# Tead_Aliens_64A_Display.net
KiCad netlist of a schematic drawn in Altium Designer
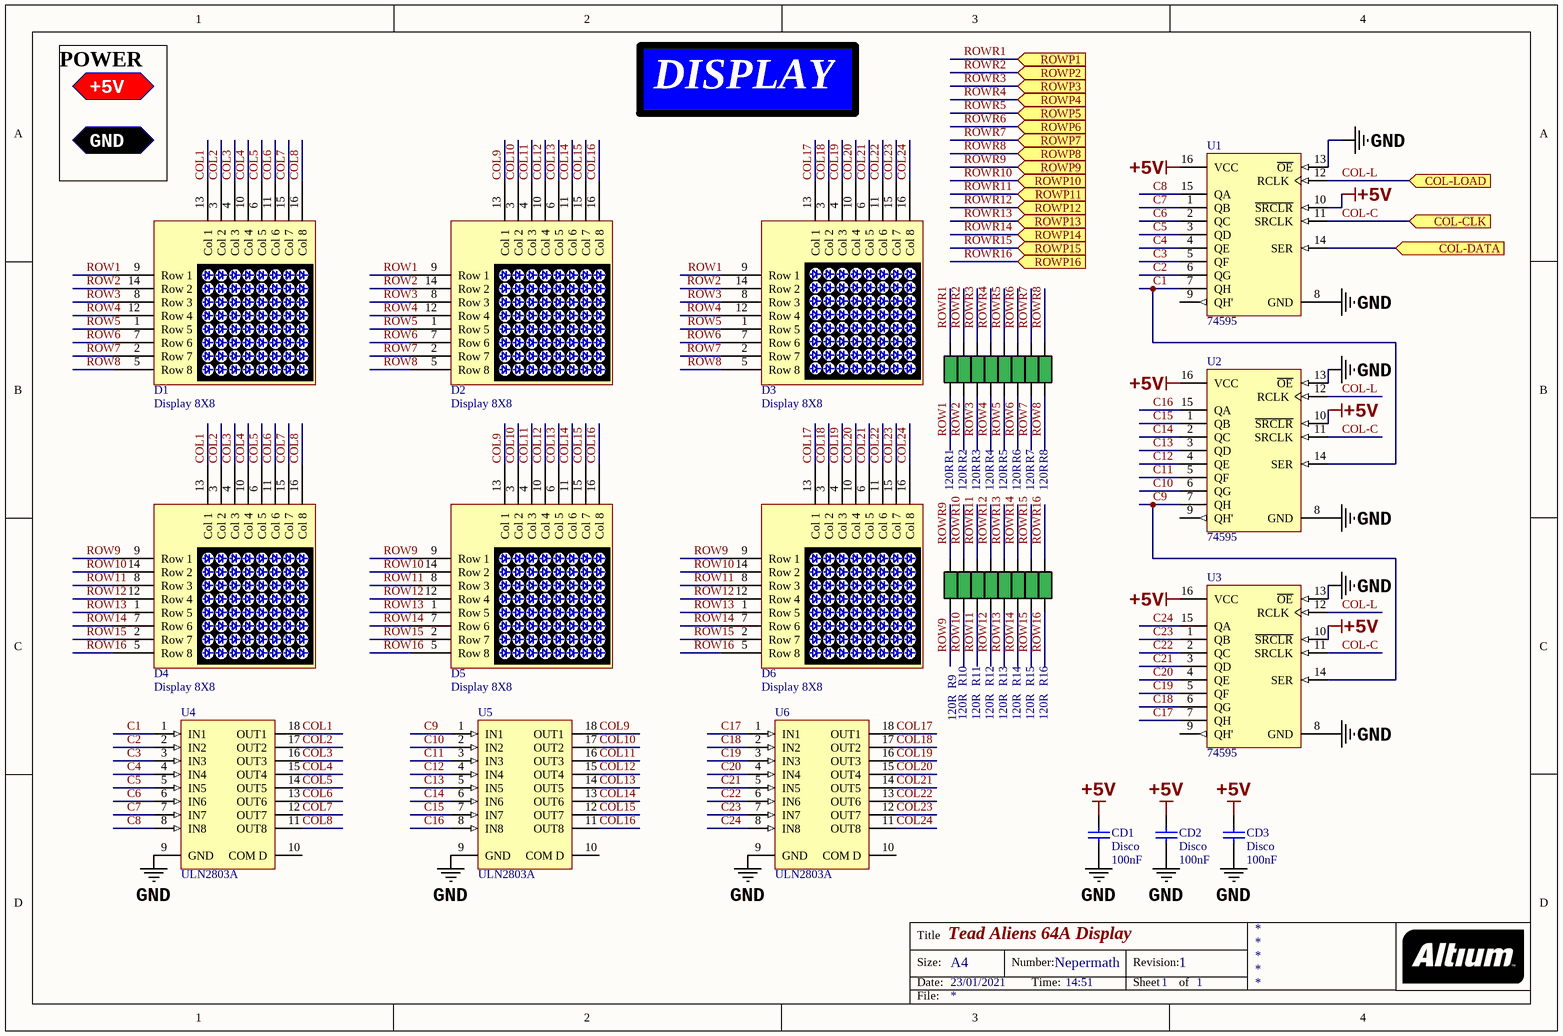
[diagram p0: Tead_Aliens_64A_Display.SchDoc]

(export (version "E")
  (design (tool "Eeschema 10.0.6"))
  (components
    (comp (ref "CD1")
      (value "Disco")
      (footprint "CAP CER DISK 3MM")
      (description "SMD Capacitor 1210 size")
      (fields (field (name "ALTIUM_VALUE") "100nF"))
      (libsource (lib "NEPERMATH") (part "CAP_DISCO"))
    )
    (comp (ref "CD2")
      (value "Disco")
      (footprint "CAP CER DISK 3MM")
      (description "SMD Capacitor 1210 size")
      (fields (field (name "ALTIUM_VALUE") "100nF"))
      (libsource (lib "NEPERMATH") (part "CAP_DISCO"))
    )
    (comp (ref "CD3")
      (value "Disco")
      (footprint "CAP CER DISK 3MM")
      (description "SMD Capacitor 1210 size")
      (fields (field (name "ALTIUM_VALUE") "100nF"))
      (libsource (lib "NEPERMATH") (part "CAP_DISCO"))
    )
    (comp (ref "D1")
      (value "Display 8X8")
      (footprint "DISPLAY_2088BS_DIP_2X8")
      (description "Display Dot LED 8x8  60mm X 60 mm")
      (libsource (lib "NEPERMATH") (part "Display 2088BS 8x8 60mm X 60 mm"))
    )
    (comp (ref "D2")
      (value "Display 8X8")
      (footprint "DISPLAY_2088BS_DIP_2X8")
      (description "Display Dot LED 8x8  60mm X 60 mm")
      (libsource (lib "NEPERMATH") (part "Display 2088BS 8x8 60mm X 60 mm"))
    )
    (comp (ref "D3")
      (value "Display 8X8")
      (footprint "DISPLAY_2088BS_DIP_2X8")
      (description "Display Dot LED 8x8  60mm X 60 mm")
      (libsource (lib "NEPERMATH") (part "Display 2088BS 8x8 60mm X 60 mm"))
    )
    (comp (ref "D4")
      (value "Display 8X8")
      (footprint "DISPLAY_2088BS_DIP_2X8")
      (description "Display Dot LED 8x8  60mm X 60 mm")
      (libsource (lib "NEPERMATH") (part "Display 2088BS 8x8 60mm X 60 mm"))
    )
    (comp (ref "D5")
      (value "Display 8X8")
      (footprint "DISPLAY_2088BS_DIP_2X8")
      (description "Display Dot LED 8x8  60mm X 60 mm")
      (libsource (lib "NEPERMATH") (part "Display 2088BS 8x8 60mm X 60 mm"))
    )
    (comp (ref "D6")
      (value "Display 8X8")
      (footprint "DISPLAY_2088BS_DIP_2X8")
      (description "Display Dot LED 8x8  60mm X 60 mm")
      (libsource (lib "NEPERMATH") (part "Display 2088BS 8x8 60mm X 60 mm"))
    )
    (comp (ref "R1")
      (value "120R")
      (footprint "RES_0805")
      (description "Generic Resistor")
      (fields (field (name "Comment") "Resistor Generic"))
      (libsource (lib "NEPERMATH") (part "Resistor Generic"))
    )
    (comp (ref "R2")
      (value "120R")
      (footprint "RES_0805")
      (description "Generic Resistor")
      (fields (field (name "Comment") "Resistor Generic"))
      (libsource (lib "NEPERMATH") (part "Resistor Generic"))
    )
    (comp (ref "R3")
      (value "120R")
      (footprint "RES_0805")
      (description "Generic Resistor")
      (fields (field (name "Comment") "Resistor Generic"))
      (libsource (lib "NEPERMATH") (part "Resistor Generic"))
    )
    (comp (ref "R4")
      (value "120R")
      (footprint "RES_0805")
      (description "Generic Resistor")
      (fields (field (name "Comment") "Resistor Generic"))
      (libsource (lib "NEPERMATH") (part "Resistor Generic"))
    )
    (comp (ref "R5")
      (value "120R")
      (footprint "RES_0805")
      (description "Generic Resistor")
      (fields (field (name "Comment") "Resistor Generic"))
      (libsource (lib "NEPERMATH") (part "Resistor Generic"))
    )
    (comp (ref "R6")
      (value "120R")
      (footprint "RES_0805")
      (description "Generic Resistor")
      (fields (field (name "Comment") "Resistor Generic"))
      (libsource (lib "NEPERMATH") (part "Resistor Generic"))
    )
    (comp (ref "R7")
      (value "120R")
      (footprint "RES_0805")
      (description "Generic Resistor")
      (fields (field (name "Comment") "Resistor Generic"))
      (libsource (lib "NEPERMATH") (part "Resistor Generic"))
    )
    (comp (ref "R8")
      (value "120R")
      (footprint "RES_0805")
      (description "Generic Resistor")
      (fields (field (name "Comment") "Resistor Generic"))
      (libsource (lib "NEPERMATH") (part "Resistor Generic"))
    )
    (comp (ref "R9")
      (value "120R")
      (footprint "RES_0805")
      (description "Generic Resistor")
      (fields (field (name "Comment") "Resistor Generic"))
      (libsource (lib "NEPERMATH") (part "Resistor Generic"))
    )
    (comp (ref "R10")
      (value "120R")
      (footprint "RES_0805")
      (description "Generic Resistor")
      (fields (field (name "Comment") "Resistor Generic"))
      (libsource (lib "NEPERMATH") (part "Resistor Generic"))
    )
    (comp (ref "R11")
      (value "120R")
      (footprint "RES_0805")
      (description "Generic Resistor")
      (fields (field (name "Comment") "Resistor Generic"))
      (libsource (lib "NEPERMATH") (part "Resistor Generic"))
    )
    (comp (ref "R12")
      (value "120R")
      (footprint "RES_0805")
      (description "Generic Resistor")
      (fields (field (name "Comment") "Resistor Generic"))
      (libsource (lib "NEPERMATH") (part "Resistor Generic"))
    )
    (comp (ref "R13")
      (value "120R")
      (footprint "RES_0805")
      (description "Generic Resistor")
      (fields (field (name "Comment") "Resistor Generic"))
      (libsource (lib "NEPERMATH") (part "Resistor Generic"))
    )
    (comp (ref "R14")
      (value "120R")
      (footprint "RES_0805")
      (description "Generic Resistor")
      (fields (field (name "Comment") "Resistor Generic"))
      (libsource (lib "NEPERMATH") (part "Resistor Generic"))
    )
    (comp (ref "R15")
      (value "120R")
      (footprint "RES_0805")
      (description "Generic Resistor")
      (fields (field (name "Comment") "Resistor Generic"))
      (libsource (lib "NEPERMATH") (part "Resistor Generic"))
    )
    (comp (ref "R16")
      (value "120R")
      (footprint "RES_0805")
      (description "Generic Resistor")
      (fields (field (name "Comment") "Resistor Generic"))
      (libsource (lib "NEPERMATH") (part "Resistor Generic"))
    )
    (comp (ref "U1")
      (value "74595")
      (footprint "DIP16")
      (description "74595 Generico L,H,LC,HC,F,LS")
      (libsource (lib "NEPERMATH") (part "74595 Generico L,H,HC,F,LS"))
    )
    (comp (ref "U2")
      (value "74595")
      (footprint "DIP16")
      (description "74595 Generico L,H,LC,HC,F,LS")
      (libsource (lib "NEPERMATH") (part "74595 Generico L,H,HC,F,LS"))
    )
    (comp (ref "U3")
      (value "74595")
      (footprint "DIP16")
      (description "74595 Generico L,H,LC,HC,F,LS")
      (libsource (lib "NEPERMATH") (part "74595 Generico L,H,HC,F,LS"))
    )
    (comp (ref "U4")
      (value "ULN2803A")
      (footprint "DIP18")
      (description "Eight Darlington Array")
      (fields (field (name "PUBLISHER") "Altium Limited"))
      (libsource (lib "NEPERMATH") (part "ULN2803A"))
    )
    (comp (ref "U5")
      (value "ULN2803A")
      (footprint "DIP18")
      (description "Eight Darlington Array")
      (fields (field (name "PUBLISHER") "Altium Limited"))
      (libsource (lib "NEPERMATH") (part "ULN2803A"))
    )
    (comp (ref "U6")
      (value "ULN2803A")
      (footprint "DIP18")
      (description "Eight Darlington Array")
      (fields (field (name "PUBLISHER") "Altium Limited"))
      (libsource (lib "NEPERMATH") (part "ULN2803A"))
    )
  )
  (nets
    (net (code "1") (name "+5V") (class "Default")
      (node (ref "CD1") (pin "1") (pinfunction "1_1") (pintype "passive"))
      (node (ref "CD2") (pin "1") (pinfunction "1_1") (pintype "passive"))
      (node (ref "CD3") (pin "1") (pinfunction "1_1") (pintype "passive"))
      (node (ref "U1") (pin "10") (pinfunction "~{SRCLR}_10") (pintype "input"))
      (node (ref "U1") (pin "16") (pinfunction "VCC_16") (pintype "power_in"))
      (node (ref "U2") (pin "10") (pinfunction "~{SRCLR}_10") (pintype "input"))
      (node (ref "U2") (pin "16") (pinfunction "VCC_16") (pintype "power_in"))
      (node (ref "U3") (pin "10") (pinfunction "~{SRCLR}_10") (pintype "input"))
      (node (ref "U3") (pin "16") (pinfunction "VCC_16") (pintype "power_in"))
    )
    (net (code "2") (name "/C1") (class "Default")
      (node (ref "U1") (pin "7") (pinfunction "QH_7") (pintype "tri_state"))
      (node (ref "U2") (pin "14") (pinfunction "SER_14") (pintype "input"))
      (node (ref "U4") (pin "1") (pinfunction "IN1_1") (pintype "input"))
    )
    (net (code "3") (name "/C2") (class "Default")
      (node (ref "U1") (pin "6") (pinfunction "QG_6") (pintype "tri_state"))
      (node (ref "U4") (pin "2") (pinfunction "IN2_2") (pintype "input"))
    )
    (net (code "4") (name "/C3") (class "Default")
      (node (ref "U1") (pin "5") (pinfunction "QF_5") (pintype "tri_state"))
      (node (ref "U4") (pin "3") (pinfunction "IN3_3") (pintype "input"))
    )
    (net (code "5") (name "/C4") (class "Default")
      (node (ref "U1") (pin "4") (pinfunction "QE_4") (pintype "tri_state"))
      (node (ref "U4") (pin "4") (pinfunction "IN4_4") (pintype "input"))
    )
    (net (code "6") (name "/C5") (class "Default")
      (node (ref "U1") (pin "3") (pinfunction "QD_3") (pintype "tri_state"))
      (node (ref "U4") (pin "5") (pinfunction "IN5_5") (pintype "input"))
    )
    (net (code "7") (name "/C6") (class "Default")
      (node (ref "U1") (pin "2") (pinfunction "QC_2") (pintype "tri_state"))
      (node (ref "U4") (pin "6") (pinfunction "IN6_6") (pintype "input"))
    )
    (net (code "8") (name "/C7") (class "Default")
      (node (ref "U1") (pin "1") (pinfunction "QB_1") (pintype "tri_state"))
      (node (ref "U4") (pin "7") (pinfunction "IN7_7") (pintype "input"))
    )
    (net (code "9") (name "/C8") (class "Default")
      (node (ref "U1") (pin "15") (pinfunction "QA_15") (pintype "tri_state"))
      (node (ref "U4") (pin "8") (pinfunction "IN8_8") (pintype "input"))
    )
    (net (code "10") (name "/C9") (class "Default")
      (node (ref "U2") (pin "7") (pinfunction "QH_7") (pintype "tri_state"))
      (node (ref "U3") (pin "14") (pinfunction "SER_14") (pintype "input"))
      (node (ref "U5") (pin "1") (pinfunction "IN1_1") (pintype "input"))
    )
    (net (code "11") (name "/C10") (class "Default")
      (node (ref "U2") (pin "6") (pinfunction "QG_6") (pintype "tri_state"))
      (node (ref "U5") (pin "2") (pinfunction "IN2_2") (pintype "input"))
    )
    (net (code "12") (name "/C11") (class "Default")
      (node (ref "U2") (pin "5") (pinfunction "QF_5") (pintype "tri_state"))
      (node (ref "U5") (pin "3") (pinfunction "IN3_3") (pintype "input"))
    )
    (net (code "13") (name "/C12") (class "Default")
      (node (ref "U2") (pin "4") (pinfunction "QE_4") (pintype "tri_state"))
      (node (ref "U5") (pin "4") (pinfunction "IN4_4") (pintype "input"))
    )
    (net (code "14") (name "/C13") (class "Default")
      (node (ref "U2") (pin "3") (pinfunction "QD_3") (pintype "tri_state"))
      (node (ref "U5") (pin "5") (pinfunction "IN5_5") (pintype "input"))
    )
    (net (code "15") (name "/C14") (class "Default")
      (node (ref "U2") (pin "2") (pinfunction "QC_2") (pintype "tri_state"))
      (node (ref "U5") (pin "6") (pinfunction "IN6_6") (pintype "input"))
    )
    (net (code "16") (name "/C15") (class "Default")
      (node (ref "U2") (pin "1") (pinfunction "QB_1") (pintype "tri_state"))
      (node (ref "U5") (pin "7") (pinfunction "IN7_7") (pintype "input"))
    )
    (net (code "17") (name "/C16") (class "Default")
      (node (ref "U2") (pin "15") (pinfunction "QA_15") (pintype "tri_state"))
      (node (ref "U5") (pin "8") (pinfunction "IN8_8") (pintype "input"))
    )
    (net (code "18") (name "/C17") (class "Default")
      (node (ref "U3") (pin "7") (pinfunction "QH_7") (pintype "tri_state"))
      (node (ref "U6") (pin "1") (pinfunction "IN1_1") (pintype "input"))
    )
    (net (code "19") (name "/C18") (class "Default")
      (node (ref "U3") (pin "6") (pinfunction "QG_6") (pintype "tri_state"))
      (node (ref "U6") (pin "2") (pinfunction "IN2_2") (pintype "input"))
    )
    (net (code "20") (name "/C19") (class "Default")
      (node (ref "U3") (pin "5") (pinfunction "QF_5") (pintype "tri_state"))
      (node (ref "U6") (pin "3") (pinfunction "IN3_3") (pintype "input"))
    )
    (net (code "21") (name "/C20") (class "Default")
      (node (ref "U3") (pin "4") (pinfunction "QE_4") (pintype "tri_state"))
      (node (ref "U6") (pin "4") (pinfunction "IN4_4") (pintype "input"))
    )
    (net (code "22") (name "/C21") (class "Default")
      (node (ref "U3") (pin "3") (pinfunction "QD_3") (pintype "tri_state"))
      (node (ref "U6") (pin "5") (pinfunction "IN5_5") (pintype "input"))
    )
    (net (code "23") (name "/C22") (class "Default")
      (node (ref "U3") (pin "2") (pinfunction "QC_2") (pintype "tri_state"))
      (node (ref "U6") (pin "6") (pinfunction "IN6_6") (pintype "input"))
    )
    (net (code "24") (name "/C23") (class "Default")
      (node (ref "U3") (pin "1") (pinfunction "QB_1") (pintype "tri_state"))
      (node (ref "U6") (pin "7") (pinfunction "IN7_7") (pintype "input"))
    )
    (net (code "25") (name "/C24") (class "Default")
      (node (ref "U3") (pin "15") (pinfunction "QA_15") (pintype "tri_state"))
      (node (ref "U6") (pin "8") (pinfunction "IN8_8") (pintype "input"))
    )
    (net (code "26") (name "/COL-C") (class "Default")
      (node (ref "U1") (pin "11") (pinfunction "SRCLK_11") (pintype "input"))
      (node (ref "U2") (pin "11") (pinfunction "SRCLK_11") (pintype "input"))
      (node (ref "U3") (pin "11") (pinfunction "SRCLK_11") (pintype "input"))
    )
    (net (code "27") (name "/COL-DATA") (class "Default")
      (node (ref "U1") (pin "14") (pinfunction "SER_14") (pintype "input"))
    )
    (net (code "28") (name "/COL-L") (class "Default")
      (node (ref "U1") (pin "12") (pinfunction "RCLK_12") (pintype "input"))
      (node (ref "U2") (pin "12") (pinfunction "RCLK_12") (pintype "input"))
      (node (ref "U3") (pin "12") (pinfunction "RCLK_12") (pintype "input"))
    )
    (net (code "29") (name "/COL1") (class "Default")
      (node (ref "D1") (pin "13") (pinfunction "Col_1_13") (pintype "passive"))
      (node (ref "D4") (pin "13") (pinfunction "Col_1_13") (pintype "passive"))
      (node (ref "U4") (pin "18") (pinfunction "OUT1_18") (pintype "open_collector"))
    )
    (net (code "30") (name "/COL2") (class "Default")
      (node (ref "D1") (pin "3") (pinfunction "Col_2_3") (pintype "passive"))
      (node (ref "D4") (pin "3") (pinfunction "Col_2_3") (pintype "passive"))
      (node (ref "U4") (pin "17") (pinfunction "OUT2_17") (pintype "open_collector"))
    )
    (net (code "31") (name "/COL3") (class "Default")
      (node (ref "D1") (pin "4") (pinfunction "Col_3_4") (pintype "passive"))
      (node (ref "D4") (pin "4") (pinfunction "Col_3_4") (pintype "passive"))
      (node (ref "U4") (pin "16") (pinfunction "OUT3_16") (pintype "open_collector"))
    )
    (net (code "32") (name "/COL4") (class "Default")
      (node (ref "D1") (pin "10") (pinfunction "Col_4_10") (pintype "passive"))
      (node (ref "D4") (pin "10") (pinfunction "Col_4_10") (pintype "passive"))
      (node (ref "U4") (pin "15") (pinfunction "OUT4_15") (pintype "open_collector"))
    )
    (net (code "33") (name "/COL5") (class "Default")
      (node (ref "D1") (pin "6") (pinfunction "Col_5_6") (pintype "passive"))
      (node (ref "D4") (pin "6") (pinfunction "Col_5_6") (pintype "passive"))
      (node (ref "U4") (pin "14") (pinfunction "OUT5_14") (pintype "open_collector"))
    )
    (net (code "34") (name "/COL6") (class "Default")
      (node (ref "D1") (pin "11") (pinfunction "Col_6_11") (pintype "passive"))
      (node (ref "D4") (pin "11") (pinfunction "Col_6_11") (pintype "passive"))
      (node (ref "U4") (pin "13") (pinfunction "OUT6_13") (pintype "open_collector"))
    )
    (net (code "35") (name "/COL7") (class "Default")
      (node (ref "D1") (pin "15") (pinfunction "Col_7_15") (pintype "passive"))
      (node (ref "D4") (pin "15") (pinfunction "Col_7_15") (pintype "passive"))
      (node (ref "U4") (pin "12") (pinfunction "OUT7_12") (pintype "open_collector"))
    )
    (net (code "36") (name "/COL8") (class "Default")
      (node (ref "D1") (pin "16") (pinfunction "Col_8_16") (pintype "passive"))
      (node (ref "D4") (pin "16") (pinfunction "Col_8_16") (pintype "passive"))
      (node (ref "U4") (pin "11") (pinfunction "OUT8_11") (pintype "open_collector"))
    )
    (net (code "37") (name "/COL9") (class "Default")
      (node (ref "D2") (pin "13") (pinfunction "Col_1_13") (pintype "passive"))
      (node (ref "D5") (pin "13") (pinfunction "Col_1_13") (pintype "passive"))
      (node (ref "U5") (pin "18") (pinfunction "OUT1_18") (pintype "open_collector"))
    )
    (net (code "38") (name "/COL10") (class "Default")
      (node (ref "D2") (pin "3") (pinfunction "Col_2_3") (pintype "passive"))
      (node (ref "D5") (pin "3") (pinfunction "Col_2_3") (pintype "passive"))
      (node (ref "U5") (pin "17") (pinfunction "OUT2_17") (pintype "open_collector"))
    )
    (net (code "39") (name "/COL11") (class "Default")
      (node (ref "D2") (pin "4") (pinfunction "Col_3_4") (pintype "passive"))
      (node (ref "D5") (pin "4") (pinfunction "Col_3_4") (pintype "passive"))
      (node (ref "U5") (pin "16") (pinfunction "OUT3_16") (pintype "open_collector"))
    )
    (net (code "40") (name "/COL12") (class "Default")
      (node (ref "D2") (pin "10") (pinfunction "Col_4_10") (pintype "passive"))
      (node (ref "D5") (pin "10") (pinfunction "Col_4_10") (pintype "passive"))
      (node (ref "U5") (pin "15") (pinfunction "OUT4_15") (pintype "open_collector"))
    )
    (net (code "41") (name "/COL13") (class "Default")
      (node (ref "D2") (pin "6") (pinfunction "Col_5_6") (pintype "passive"))
      (node (ref "D5") (pin "6") (pinfunction "Col_5_6") (pintype "passive"))
      (node (ref "U5") (pin "14") (pinfunction "OUT5_14") (pintype "open_collector"))
    )
    (net (code "42") (name "/COL14") (class "Default")
      (node (ref "D2") (pin "11") (pinfunction "Col_6_11") (pintype "passive"))
      (node (ref "D5") (pin "11") (pinfunction "Col_6_11") (pintype "passive"))
      (node (ref "U5") (pin "13") (pinfunction "OUT6_13") (pintype "open_collector"))
    )
    (net (code "43") (name "/COL15") (class "Default")
      (node (ref "D2") (pin "15") (pinfunction "Col_7_15") (pintype "passive"))
      (node (ref "D5") (pin "15") (pinfunction "Col_7_15") (pintype "passive"))
      (node (ref "U5") (pin "12") (pinfunction "OUT7_12") (pintype "open_collector"))
    )
    (net (code "44") (name "/COL16") (class "Default")
      (node (ref "D2") (pin "16") (pinfunction "Col_8_16") (pintype "passive"))
      (node (ref "D5") (pin "16") (pinfunction "Col_8_16") (pintype "passive"))
      (node (ref "U5") (pin "11") (pinfunction "OUT8_11") (pintype "open_collector"))
    )
    (net (code "45") (name "/COL17") (class "Default")
      (node (ref "D3") (pin "13") (pinfunction "Col_1_13") (pintype "passive"))
      (node (ref "D6") (pin "13") (pinfunction "Col_1_13") (pintype "passive"))
      (node (ref "U6") (pin "18") (pinfunction "OUT1_18") (pintype "open_collector"))
    )
    (net (code "46") (name "/COL18") (class "Default")
      (node (ref "D3") (pin "3") (pinfunction "Col_2_3") (pintype "passive"))
      (node (ref "D6") (pin "3") (pinfunction "Col_2_3") (pintype "passive"))
      (node (ref "U6") (pin "17") (pinfunction "OUT2_17") (pintype "open_collector"))
    )
    (net (code "47") (name "/COL19") (class "Default")
      (node (ref "D3") (pin "4") (pinfunction "Col_3_4") (pintype "passive"))
      (node (ref "D6") (pin "4") (pinfunction "Col_3_4") (pintype "passive"))
      (node (ref "U6") (pin "16") (pinfunction "OUT3_16") (pintype "open_collector"))
    )
    (net (code "48") (name "/COL20") (class "Default")
      (node (ref "D3") (pin "10") (pinfunction "Col_4_10") (pintype "passive"))
      (node (ref "D6") (pin "10") (pinfunction "Col_4_10") (pintype "passive"))
      (node (ref "U6") (pin "15") (pinfunction "OUT4_15") (pintype "open_collector"))
    )
    (net (code "49") (name "/COL21") (class "Default")
      (node (ref "D3") (pin "6") (pinfunction "Col_5_6") (pintype "passive"))
      (node (ref "D6") (pin "6") (pinfunction "Col_5_6") (pintype "passive"))
      (node (ref "U6") (pin "14") (pinfunction "OUT5_14") (pintype "open_collector"))
    )
    (net (code "50") (name "/COL22") (class "Default")
      (node (ref "D3") (pin "11") (pinfunction "Col_6_11") (pintype "passive"))
      (node (ref "D6") (pin "11") (pinfunction "Col_6_11") (pintype "passive"))
      (node (ref "U6") (pin "13") (pinfunction "OUT6_13") (pintype "open_collector"))
    )
    (net (code "51") (name "/COL23") (class "Default")
      (node (ref "D3") (pin "15") (pinfunction "Col_7_15") (pintype "passive"))
      (node (ref "D6") (pin "15") (pinfunction "Col_7_15") (pintype "passive"))
      (node (ref "U6") (pin "12") (pinfunction "OUT7_12") (pintype "open_collector"))
    )
    (net (code "52") (name "/COL24") (class "Default")
      (node (ref "D3") (pin "16") (pinfunction "Col_8_16") (pintype "passive"))
      (node (ref "D6") (pin "16") (pinfunction "Col_8_16") (pintype "passive"))
      (node (ref "U6") (pin "11") (pinfunction "OUT8_11") (pintype "open_collector"))
    )
    (net (code "53") (name "/ROW1") (class "Default")
      (node (ref "D1") (pin "9") (pinfunction "Row_1_9") (pintype "passive"))
      (node (ref "D2") (pin "9") (pinfunction "Row_1_9") (pintype "passive"))
      (node (ref "D3") (pin "9") (pinfunction "Row_1_9") (pintype "passive"))
      (node (ref "R1") (pin "1") (pinfunction "1_1") (pintype "passive"))
    )
    (net (code "54") (name "/ROW2") (class "Default")
      (node (ref "D1") (pin "14") (pinfunction "Row_2_14") (pintype "passive"))
      (node (ref "D2") (pin "14") (pinfunction "Row_2_14") (pintype "passive"))
      (node (ref "D3") (pin "14") (pinfunction "Row_2_14") (pintype "passive"))
      (node (ref "R2") (pin "1") (pinfunction "1_1") (pintype "passive"))
    )
    (net (code "55") (name "/ROW3") (class "Default")
      (node (ref "D1") (pin "8") (pinfunction "Row_3_8") (pintype "passive"))
      (node (ref "D2") (pin "8") (pinfunction "Row_3_8") (pintype "passive"))
      (node (ref "D3") (pin "8") (pinfunction "Row_3_8") (pintype "passive"))
      (node (ref "R3") (pin "1") (pinfunction "1_1") (pintype "passive"))
    )
    (net (code "56") (name "/ROW4") (class "Default")
      (node (ref "D1") (pin "12") (pinfunction "Row_4_12") (pintype "passive"))
      (node (ref "D2") (pin "12") (pinfunction "Row_4_12") (pintype "passive"))
      (node (ref "D3") (pin "12") (pinfunction "Row_4_12") (pintype "passive"))
      (node (ref "R4") (pin "1") (pinfunction "1_1") (pintype "passive"))
    )
    (net (code "57") (name "/ROW5") (class "Default")
      (node (ref "D1") (pin "1") (pinfunction "Row_5_1") (pintype "passive"))
      (node (ref "D2") (pin "1") (pinfunction "Row_5_1") (pintype "passive"))
      (node (ref "D3") (pin "1") (pinfunction "Row_5_1") (pintype "passive"))
      (node (ref "R5") (pin "1") (pinfunction "1_1") (pintype "passive"))
    )
    (net (code "58") (name "/ROW6") (class "Default")
      (node (ref "D1") (pin "7") (pinfunction "Row_6_7") (pintype "passive"))
      (node (ref "D2") (pin "7") (pinfunction "Row_6_7") (pintype "passive"))
      (node (ref "D3") (pin "7") (pinfunction "Row_6_7") (pintype "passive"))
      (node (ref "R6") (pin "1") (pinfunction "1_1") (pintype "passive"))
    )
    (net (code "59") (name "/ROW7") (class "Default")
      (node (ref "D1") (pin "2") (pinfunction "Row_7_2") (pintype "passive"))
      (node (ref "D2") (pin "2") (pinfunction "Row_7_2") (pintype "passive"))
      (node (ref "D3") (pin "2") (pinfunction "Row_7_2") (pintype "passive"))
      (node (ref "R7") (pin "1") (pinfunction "1_1") (pintype "passive"))
    )
    (net (code "60") (name "/ROW8") (class "Default")
      (node (ref "D1") (pin "5") (pinfunction "Row_8_5") (pintype "passive"))
      (node (ref "D2") (pin "5") (pinfunction "Row_8_5") (pintype "passive"))
      (node (ref "D3") (pin "5") (pinfunction "Row_8_5") (pintype "passive"))
      (node (ref "R8") (pin "1") (pinfunction "1_1") (pintype "passive"))
    )
    (net (code "61") (name "/ROW9") (class "Default")
      (node (ref "D4") (pin "9") (pinfunction "Row_1_9") (pintype "passive"))
      (node (ref "D5") (pin "9") (pinfunction "Row_1_9") (pintype "passive"))
      (node (ref "D6") (pin "9") (pinfunction "Row_1_9") (pintype "passive"))
      (node (ref "R9") (pin "1") (pinfunction "1_1") (pintype "passive"))
    )
    (net (code "62") (name "/ROW10") (class "Default")
      (node (ref "D4") (pin "14") (pinfunction "Row_2_14") (pintype "passive"))
      (node (ref "D5") (pin "14") (pinfunction "Row_2_14") (pintype "passive"))
      (node (ref "D6") (pin "14") (pinfunction "Row_2_14") (pintype "passive"))
      (node (ref "R10") (pin "1") (pinfunction "1_1") (pintype "passive"))
    )
    (net (code "63") (name "/ROW11") (class "Default")
      (node (ref "D4") (pin "8") (pinfunction "Row_3_8") (pintype "passive"))
      (node (ref "D5") (pin "8") (pinfunction "Row_3_8") (pintype "passive"))
      (node (ref "D6") (pin "8") (pinfunction "Row_3_8") (pintype "passive"))
      (node (ref "R11") (pin "1") (pinfunction "1_1") (pintype "passive"))
    )
    (net (code "64") (name "/ROW12") (class "Default")
      (node (ref "D4") (pin "12") (pinfunction "Row_4_12") (pintype "passive"))
      (node (ref "D5") (pin "12") (pinfunction "Row_4_12") (pintype "passive"))
      (node (ref "D6") (pin "12") (pinfunction "Row_4_12") (pintype "passive"))
      (node (ref "R12") (pin "1") (pinfunction "1_1") (pintype "passive"))
    )
    (net (code "65") (name "/ROW13") (class "Default")
      (node (ref "D4") (pin "1") (pinfunction "Row_5_1") (pintype "passive"))
      (node (ref "D5") (pin "1") (pinfunction "Row_5_1") (pintype "passive"))
      (node (ref "D6") (pin "1") (pinfunction "Row_5_1") (pintype "passive"))
      (node (ref "R13") (pin "1") (pinfunction "1_1") (pintype "passive"))
    )
    (net (code "66") (name "/ROW14") (class "Default")
      (node (ref "D4") (pin "7") (pinfunction "Row_6_7") (pintype "passive"))
      (node (ref "D5") (pin "7") (pinfunction "Row_6_7") (pintype "passive"))
      (node (ref "D6") (pin "7") (pinfunction "Row_6_7") (pintype "passive"))
      (node (ref "R14") (pin "1") (pinfunction "1_1") (pintype "passive"))
    )
    (net (code "67") (name "/ROW15") (class "Default")
      (node (ref "D4") (pin "2") (pinfunction "Row_7_2") (pintype "passive"))
      (node (ref "D5") (pin "2") (pinfunction "Row_7_2") (pintype "passive"))
      (node (ref "D6") (pin "2") (pinfunction "Row_7_2") (pintype "passive"))
      (node (ref "R15") (pin "1") (pinfunction "1_1") (pintype "passive"))
    )
    (net (code "68") (name "/ROW16") (class "Default")
      (node (ref "D4") (pin "5") (pinfunction "Row_8_5") (pintype "passive"))
      (node (ref "D5") (pin "5") (pinfunction "Row_8_5") (pintype "passive"))
      (node (ref "D6") (pin "5") (pinfunction "Row_8_5") (pintype "passive"))
      (node (ref "R16") (pin "1") (pinfunction "1_1") (pintype "passive"))
    )
    (net (code "69") (name "/ROWR1") (class "Default")
      (node (ref "R1") (pin "2") (pinfunction "2_2") (pintype "passive"))
    )
    (net (code "70") (name "/ROWR2") (class "Default")
      (node (ref "R2") (pin "2") (pinfunction "2_2") (pintype "passive"))
    )
    (net (code "71") (name "/ROWR3") (class "Default")
      (node (ref "R3") (pin "2") (pinfunction "2_2") (pintype "passive"))
    )
    (net (code "72") (name "/ROWR4") (class "Default")
      (node (ref "R4") (pin "2") (pinfunction "2_2") (pintype "passive"))
    )
    (net (code "73") (name "/ROWR5") (class "Default")
      (node (ref "R5") (pin "2") (pinfunction "2_2") (pintype "passive"))
    )
    (net (code "74") (name "/ROWR6") (class "Default")
      (node (ref "R6") (pin "2") (pinfunction "2_2") (pintype "passive"))
    )
    (net (code "75") (name "/ROWR7") (class "Default")
      (node (ref "R7") (pin "2") (pinfunction "2_2") (pintype "passive"))
    )
    (net (code "76") (name "/ROWR8") (class "Default")
      (node (ref "R8") (pin "2") (pinfunction "2_2") (pintype "passive"))
    )
    (net (code "77") (name "/ROWR9") (class "Default")
      (node (ref "R9") (pin "2") (pinfunction "2_2") (pintype "passive"))
    )
    (net (code "78") (name "/ROWR10") (class "Default")
      (node (ref "R10") (pin "2") (pinfunction "2_2") (pintype "passive"))
    )
    (net (code "79") (name "/ROWR11") (class "Default")
      (node (ref "R11") (pin "2") (pinfunction "2_2") (pintype "passive"))
    )
    (net (code "80") (name "/ROWR12") (class "Default")
      (node (ref "R12") (pin "2") (pinfunction "2_2") (pintype "passive"))
    )
    (net (code "81") (name "/ROWR13") (class "Default")
      (node (ref "R13") (pin "2") (pinfunction "2_2") (pintype "passive"))
    )
    (net (code "82") (name "/ROWR14") (class "Default")
      (node (ref "R14") (pin "2") (pinfunction "2_2") (pintype "passive"))
    )
    (net (code "83") (name "/ROWR15") (class "Default")
      (node (ref "R15") (pin "2") (pinfunction "2_2") (pintype "passive"))
    )
    (net (code "84") (name "/ROWR16") (class "Default")
      (node (ref "R16") (pin "2") (pinfunction "2_2") (pintype "passive"))
    )
    (net (code "85") (name "GND") (class "Default")
      (node (ref "CD1") (pin "2") (pinfunction "2_2") (pintype "passive"))
      (node (ref "CD2") (pin "2") (pinfunction "2_2") (pintype "passive"))
      (node (ref "CD3") (pin "2") (pinfunction "2_2") (pintype "passive"))
      (node (ref "U1") (pin "13") (pinfunction "~{OE}_13") (pintype "input"))
      (node (ref "U1") (pin "8") (pinfunction "GND_8") (pintype "power_in"))
      (node (ref "U2") (pin "13") (pinfunction "~{OE}_13") (pintype "input"))
      (node (ref "U2") (pin "8") (pinfunction "GND_8") (pintype "power_in"))
      (node (ref "U3") (pin "13") (pinfunction "~{OE}_13") (pintype "input"))
      (node (ref "U3") (pin "8") (pinfunction "GND_8") (pintype "power_in"))
      (node (ref "U4") (pin "9") (pinfunction "GND_9") (pintype "power_in"))
      (node (ref "U5") (pin "9") (pinfunction "GND_9") (pintype "power_in"))
      (node (ref "U6") (pin "9") (pinfunction "GND_9") (pintype "power_in"))
    )
    (net (code "86") (name "unconnected-(U1-QH'-Pad9)") (class "Default")
      (node (ref "U1") (pin "9") (pinfunction "QH'_9") (pintype "output"))
    )
    (net (code "87") (name "unconnected-(U2-QH'-Pad9)") (class "Default")
      (node (ref "U2") (pin "9") (pinfunction "QH'_9") (pintype "output"))
    )
    (net (code "88") (name "unconnected-(U3-QH'-Pad9)") (class "Default")
      (node (ref "U3") (pin "9") (pinfunction "QH'_9") (pintype "output"))
    )
    (net (code "89") (name "unconnected-(U4-COM_D-Pad10)") (class "Default")
      (node (ref "U4") (pin "10") (pinfunction "COM_D_10") (pintype "passive"))
    )
    (net (code "90") (name "unconnected-(U5-COM_D-Pad10)") (class "Default")
      (node (ref "U5") (pin "10") (pinfunction "COM_D_10") (pintype "passive"))
    )
    (net (code "91") (name "unconnected-(U6-COM_D-Pad10)") (class "Default")
      (node (ref "U6") (pin "10") (pinfunction "COM_D_10") (pintype "passive"))
    )
  )
)
